# PCB_Vigne_Periph.net
KiCad netlist of a schematic drawn in Altium Designer
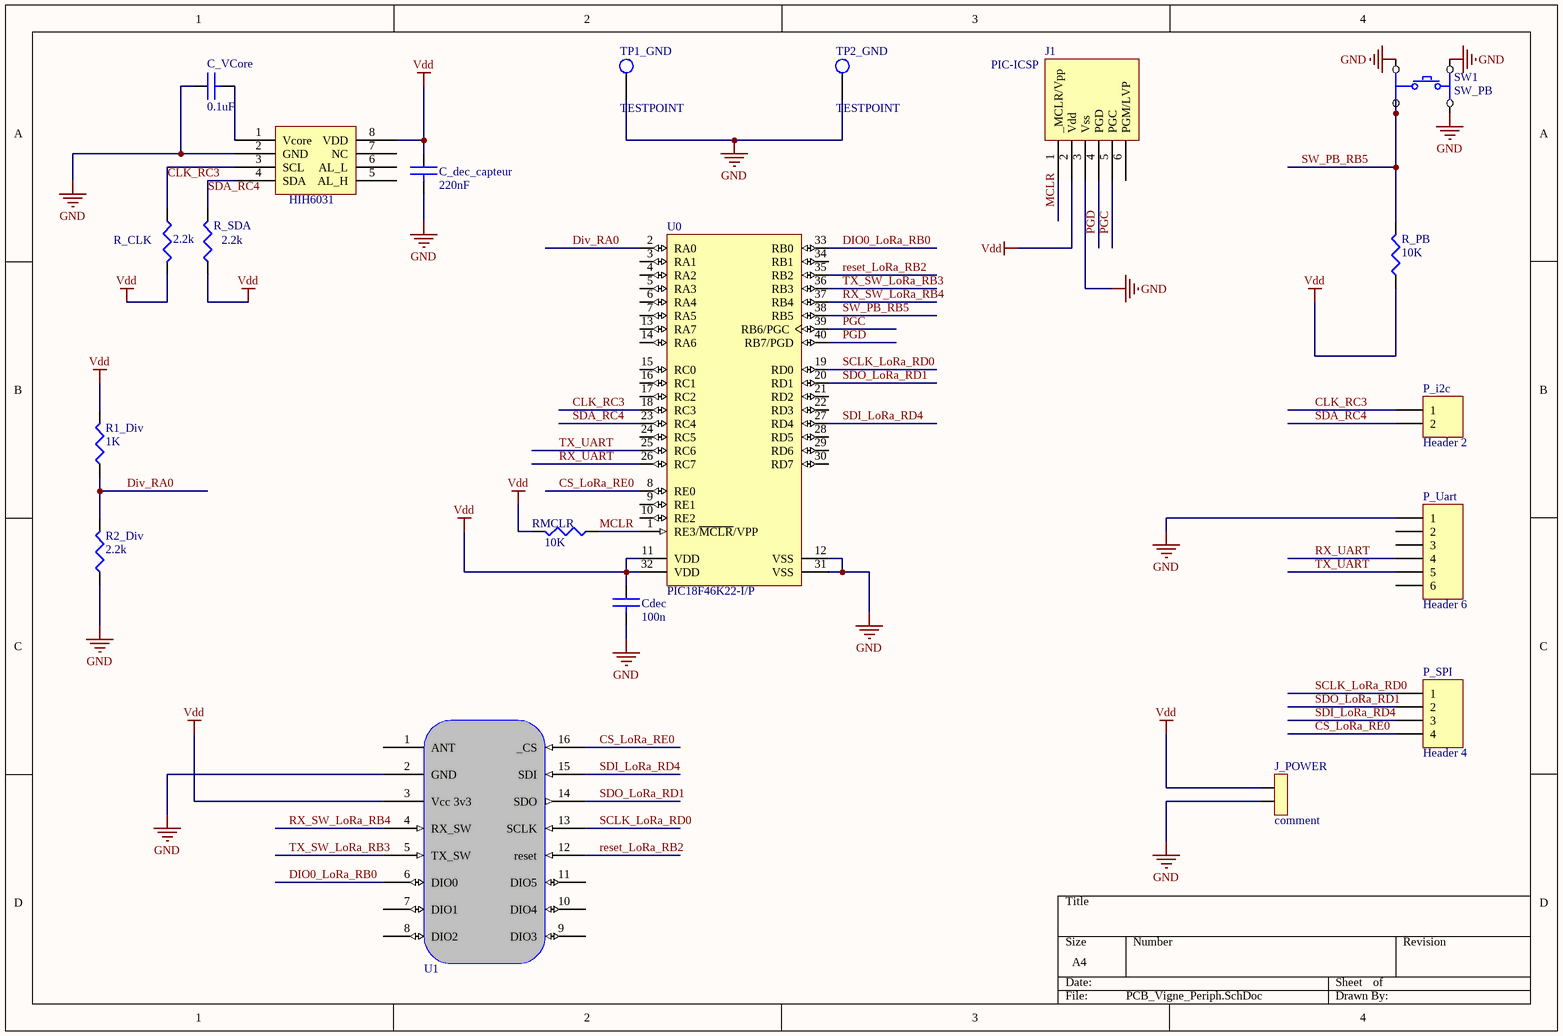
[diagram p0: PCB_Vigne_Periph.SchDoc]

(export (version "E")
  (design (tool "Eeschema 10.0.6"))
  (components
    (comp (ref "Cdec")
      (value "100n")
      (footprint "RAD0.2")
      (description "capacité non polarisée")
      (fields (field (name "Comment") "CAP"))
      (libsource (lib "ISEN_basics") (part "CAP"))
    )
    (comp (ref "C_dec_capteur")
      (value "220nF")
      (footprint "RAD0.2")
      (description "capacité non polarisée")
      (fields (field (name "Comment") "CAP"))
      (libsource (lib "ISEN_basics") (part "CAP"))
    )
    (comp (ref "C_VCore")
      (value "0.1uF")
      (footprint "RAD0.2")
      (description "capacité non polarisée")
      (fields (field (name "Comment") "CAP"))
      (libsource (lib "ISEN_basics") (part "CAP"))
    )
    (comp (ref "HIH6031")
      (value "HIH6031")
      (footprint "HIH6031-Traversant")
      (libsource (lib "HIH6031") (part "HIH6031"))
    )
    (comp (ref "J1")
      (value "PIC-ICSP")
      (footprint "PIC-ICSP")
      (libsource (lib "ISEN_basics") (part "PIC-ICSP"))
    )
    (comp (ref "J_POWER")
      (value "comment")
      (footprint "AMP_2")
      (description "connecteur alim 2 pôles")
      (libsource (lib "ISEN_basics") (part "POWER2"))
    )
    (comp (ref "P_i2c")
      (value "Header 2")
      (footprint "HDR1X2")
      (description "Header, 2-Pin")
      (fields (field (name "PUBLISHER") "Altium Limited"))
      (libsource (lib "Miscellaneous Connectors") (part "Header 2"))
    )
    (comp (ref "P_SPI")
      (value "Header 4")
      (footprint "HDR1X4")
      (description "Header, 4-Pin")
      (fields (field (name "PUBLISHER") "Altium Limited"))
      (libsource (lib "Miscellaneous Connectors") (part "Header 4"))
    )
    (comp (ref "P_Uart")
      (value "Header 6")
      (footprint "HDR1X6")
      (description "Header, 6-Pin")
      (fields (field (name "PUBLISHER") "Altium Limited"))
      (libsource (lib "Miscellaneous Connectors") (part "Header 6"))
    )
    (comp (ref "R1_Div")
      (value "1K")
      (footprint "AXIAL0.4")
      (description "resistance")
      (fields (field (name "Comment") "RES"))
      (libsource (lib "ISEN_basics") (part "RES"))
    )
    (comp (ref "R2_Div")
      (value "2.2k")
      (footprint "AXIAL0.4")
      (description "resistance")
      (fields (field (name "Comment") "RES"))
      (libsource (lib "ISEN_basics") (part "RES"))
    )
    (comp (ref "RMCLR")
      (value "10K")
      (footprint "AXIAL0.4")
      (description "resistance")
      (fields (field (name "Comment") "RES"))
      (libsource (lib "ISEN_basicsIntLib") (part "RES"))
    )
    (comp (ref "R_CLK")
      (value "2.2k")
      (footprint "AXIAL0.4")
      (description "resistance")
      (fields (field (name "Comment") "RES"))
      (libsource (lib "ISEN_basics") (part "RES"))
    )
    (comp (ref "R_PB")
      (value "10K")
      (footprint "AXIAL0.4")
      (description "resistance")
      (fields (field (name "Comment") "RES"))
      (libsource (lib "ISEN_basics") (part "RES"))
    )
    (comp (ref "R_SDA")
      (value "2.2k")
      (footprint "AXIAL0.4")
      (description "resistance")
      (fields (field (name "Comment") "RES"))
      (libsource (lib "ISEN_basics") (part "RES"))
    )
    (comp (ref "SW1") (value "SW_PB") (footprint "KSA") (libsource (lib "ISEN_basics") (part "SW_PB")))
    (comp (ref "TP1_GND")
      (value "TESTPOINT")
      (footprint "testpoint")
      (libsource (lib "ISEN_basics") (part "TESTPOINT"))
    )
    (comp (ref "TP2_GND")
      (value "TESTPOINT")
      (footprint "testpoint")
      (libsource (lib "ISEN_basics") (part "TESTPOINT"))
    )
    (comp (ref "U0")
      (value "PIC18F46K22-I/P")
      (footprint "MCHP-PDIP-P40")
      (fields (field (name "MANUFACTURER") "Microchip"))
      (libsource (lib "Microchip PIC18") (part "PIC18F46K22-I/P"))
    )
    (comp (ref "U1")
      (value "RF-LORA-868-SO")
      (footprint "RF-LORA-868-DIP")
      (libsource (lib "ISEN_basics") (part "RF-LORA-868-SO"))
    )
  )
  (nets
    (net (code "1") (name "/CLK_RC3") (class "Default")
      (node (ref "HIH6031") (pin "3") (pinfunction "SCL_3") (pintype "passive"))
      (node (ref "P_i2c") (pin "1") (pinfunction "1_1") (pintype "passive"))
      (node (ref "R_CLK") (pin "1") (pintype "passive"))
      (node (ref "U0") (pin "18") (pinfunction "RC3_18") (pintype "bidirectional"))
    )
    (net (code "2") (name "/CS_LoRa_RE0") (class "Default")
      (node (ref "P_SPI") (pin "4") (pinfunction "4_4") (pintype "passive"))
      (node (ref "U0") (pin "8") (pinfunction "RE0_8") (pintype "bidirectional"))
      (node (ref "U1") (pin "16") (pinfunction "_CS_16") (pintype "input"))
    )
    (net (code "3") (name "/DIO0_LoRa_RB0") (class "Default")
      (node (ref "U0") (pin "33") (pinfunction "RB0_33") (pintype "bidirectional"))
      (node (ref "U1") (pin "6") (pinfunction "DIO0_6") (pintype "bidirectional"))
    )
    (net (code "4") (name "/Div_RA0") (class "Default")
      (node (ref "R1_Div") (pin "1") (pintype "passive"))
      (node (ref "R2_Div") (pin "2") (pintype "passive"))
      (node (ref "U0") (pin "2") (pinfunction "RA0_2") (pintype "bidirectional"))
    )
    (net (code "5") (name "/MCLR") (class "Default")
      (node (ref "J1") (pin "1") (pinfunction "_MCLR/Vpp_1") (pintype "passive"))
      (node (ref "RMCLR") (pin "1") (pintype "passive"))
      (node (ref "U0") (pin "1") (pinfunction "RE3/~{MCLR}/VPP_1") (pintype "input"))
    )
    (net (code "6") (name "/PGC") (class "Default")
      (node (ref "J1") (pin "5") (pinfunction "PGC_5") (pintype "passive"))
      (node (ref "U0") (pin "39") (pinfunction "RB6/PGC_39") (pintype "bidirectional"))
    )
    (net (code "7") (name "/PGD") (class "Default")
      (node (ref "J1") (pin "4") (pinfunction "PGD_4") (pintype "passive"))
      (node (ref "U0") (pin "40") (pinfunction "RB7/PGD_40") (pintype "bidirectional"))
    )
    (net (code "8") (name "/RX_SW_LoRa_RB4") (class "Default")
      (node (ref "U0") (pin "37") (pinfunction "RB4_37") (pintype "bidirectional"))
      (node (ref "U1") (pin "4") (pinfunction "RX_SW_4") (pintype "input"))
    )
    (net (code "9") (name "/RX_UART") (class "Default")
      (node (ref "P_Uart") (pin "4") (pinfunction "4_4") (pintype "passive"))
      (node (ref "U0") (pin "26") (pinfunction "RC7_26") (pintype "bidirectional"))
    )
    (net (code "10") (name "/SCLK_LoRa_RD0") (class "Default")
      (node (ref "P_SPI") (pin "1") (pinfunction "1_1") (pintype "passive"))
      (node (ref "U0") (pin "19") (pinfunction "RD0_19") (pintype "bidirectional"))
      (node (ref "U1") (pin "13") (pinfunction "SCLK_13") (pintype "input"))
    )
    (net (code "11") (name "/SDA_RC4") (class "Default")
      (node (ref "HIH6031") (pin "4") (pinfunction "SDA_4") (pintype "passive"))
      (node (ref "P_i2c") (pin "2") (pinfunction "2_2") (pintype "passive"))
      (node (ref "R_SDA") (pin "2") (pintype "passive"))
      (node (ref "U0") (pin "23") (pinfunction "RC4_23") (pintype "bidirectional"))
    )
    (net (code "12") (name "/SDI_LoRa_RD4") (class "Default")
      (node (ref "P_SPI") (pin "3") (pinfunction "3_3") (pintype "passive"))
      (node (ref "U0") (pin "27") (pinfunction "RD4_27") (pintype "bidirectional"))
      (node (ref "U1") (pin "15") (pinfunction "SDI_15") (pintype "input"))
    )
    (net (code "13") (name "/SDO_LoRa_RD1") (class "Default")
      (node (ref "P_SPI") (pin "2") (pinfunction "2_2") (pintype "passive"))
      (node (ref "U0") (pin "20") (pinfunction "RD1_20") (pintype "bidirectional"))
      (node (ref "U1") (pin "14") (pinfunction "SDO_14") (pintype "output"))
    )
    (net (code "14") (name "/SW_PB_RB5") (class "Default")
      (node (ref "R_PB") (pin "2") (pintype "passive"))
      (node (ref "SW1") (pin "2") (pintype "passive"))
      (node (ref "U0") (pin "38") (pinfunction "RB5_38") (pintype "bidirectional"))
    )
    (net (code "15") (name "/TX_SW_LoRa_RB3") (class "Default")
      (node (ref "U0") (pin "36") (pinfunction "RB3_36") (pintype "bidirectional"))
      (node (ref "U1") (pin "5") (pinfunction "TX_SW_5") (pintype "input"))
    )
    (net (code "16") (name "/TX_UART") (class "Default")
      (node (ref "P_Uart") (pin "5") (pinfunction "5_5") (pintype "passive"))
      (node (ref "U0") (pin "25") (pinfunction "RC6_25") (pintype "bidirectional"))
    )
    (net (code "17") (name "/reset_LoRa_RB2") (class "Default")
      (node (ref "U0") (pin "35") (pinfunction "RB2_35") (pintype "bidirectional"))
      (node (ref "U1") (pin "12") (pinfunction "reset_12") (pintype "input"))
    )
    (net (code "18") (name "GND") (class "Default")
      (node (ref "C_VCore") (pin "1") (pinfunction "1_1") (pintype "passive"))
      (node (ref "C_dec_capteur") (pin "2") (pinfunction "2_2") (pintype "passive"))
      (node (ref "Cdec") (pin "2") (pinfunction "2_2") (pintype "passive"))
      (node (ref "HIH6031") (pin "2") (pinfunction "GND_2") (pintype "passive"))
      (node (ref "J1") (pin "3") (pinfunction "Vss_3") (pintype "passive"))
      (node (ref "J_POWER") (pin "1") (pintype "passive"))
      (node (ref "P_Uart") (pin "1") (pinfunction "1_1") (pintype "passive"))
      (node (ref "R2_Div") (pin "1") (pintype "passive"))
      (node (ref "SW1") (pin "1") (pintype "passive"))
      (node (ref "SW1") (pin "3") (pintype "passive"))
      (node (ref "SW1") (pin "4") (pintype "passive"))
      (node (ref "TP1_GND") (pin "1") (pintype "passive"))
      (node (ref "TP2_GND") (pin "1") (pintype "passive"))
      (node (ref "U0") (pin "12") (pinfunction "VSS_12") (pintype "power_in"))
      (node (ref "U0") (pin "31") (pinfunction "VSS_31") (pintype "power_in"))
      (node (ref "U1") (pin "2") (pinfunction "GND_2") (pintype "power_in"))
    )
    (net (code "19") (name "Net-(HIH6031-Vcore)") (class "Default")
      (node (ref "C_VCore") (pin "2") (pinfunction "2_2") (pintype "passive"))
      (node (ref "HIH6031") (pin "1") (pinfunction "Vcore_1") (pintype "passive"))
    )
    (net (code "20") (name "Vdd") (class "Default")
      (node (ref "C_dec_capteur") (pin "1") (pinfunction "1_1") (pintype "passive"))
      (node (ref "Cdec") (pin "1") (pinfunction "1_1") (pintype "passive"))
      (node (ref "HIH6031") (pin "8") (pinfunction "VDD_8") (pintype "passive"))
      (node (ref "J1") (pin "2") (pinfunction "Vdd_2") (pintype "passive"))
      (node (ref "J_POWER") (pin "2") (pintype "passive"))
      (node (ref "R1_Div") (pin "2") (pintype "passive"))
      (node (ref "RMCLR") (pin "2") (pintype "passive"))
      (node (ref "R_CLK") (pin "2") (pintype "passive"))
      (node (ref "R_PB") (pin "1") (pintype "passive"))
      (node (ref "R_SDA") (pin "1") (pintype "passive"))
      (node (ref "U0") (pin "11") (pinfunction "VDD_11") (pintype "power_in"))
      (node (ref "U0") (pin "32") (pinfunction "VDD_32") (pintype "power_in"))
      (node (ref "U1") (pin "3") (pinfunction "Vcc_3v3_3") (pintype "power_in"))
    )
    (net (code "21") (name "unconnected-(HIH6031-AL_H-Pad5)") (class "Default")
      (node (ref "HIH6031") (pin "5") (pinfunction "AL_H_5") (pintype "passive"))
    )
    (net (code "22") (name "unconnected-(HIH6031-AL_L-Pad6)") (class "Default")
      (node (ref "HIH6031") (pin "6") (pinfunction "AL_L_6") (pintype "passive"))
    )
    (net (code "23") (name "unconnected-(HIH6031-NC-Pad7)") (class "Default")
      (node (ref "HIH6031") (pin "7") (pinfunction "NC_7") (pintype "passive"))
    )
    (net (code "24") (name "unconnected-(J1-PGM{slash}LVP-Pad6)") (class "Default")
      (node (ref "J1") (pin "6") (pinfunction "PGM/LVP_6") (pintype "passive"))
    )
    (net (code "25") (name "unconnected-(P_Uart-Pad2)") (class "Default")
      (node (ref "P_Uart") (pin "2") (pinfunction "2_2") (pintype "passive"))
    )
    (net (code "26") (name "unconnected-(P_Uart-Pad3)") (class "Default")
      (node (ref "P_Uart") (pin "3") (pinfunction "3_3") (pintype "passive"))
    )
    (net (code "27") (name "unconnected-(P_Uart-Pad6)") (class "Default")
      (node (ref "P_Uart") (pin "6") (pinfunction "6_6") (pintype "passive"))
    )
    (net (code "28") (name "unconnected-(U0-RA1-Pad3)") (class "Default")
      (node (ref "U0") (pin "3") (pinfunction "RA1_3") (pintype "bidirectional"))
    )
    (net (code "29") (name "unconnected-(U0-RA2-Pad4)") (class "Default")
      (node (ref "U0") (pin "4") (pinfunction "RA2_4") (pintype "bidirectional"))
    )
    (net (code "30") (name "unconnected-(U0-RA3-Pad5)") (class "Default")
      (node (ref "U0") (pin "5") (pinfunction "RA3_5") (pintype "bidirectional"))
    )
    (net (code "31") (name "unconnected-(U0-RA4-Pad6)") (class "Default")
      (node (ref "U0") (pin "6") (pinfunction "RA4_6") (pintype "bidirectional"))
    )
    (net (code "32") (name "unconnected-(U0-RA5-Pad7)") (class "Default")
      (node (ref "U0") (pin "7") (pinfunction "RA5_7") (pintype "bidirectional"))
    )
    (net (code "33") (name "unconnected-(U0-RA6-Pad14)") (class "Default")
      (node (ref "U0") (pin "14") (pinfunction "RA6_14") (pintype "bidirectional"))
    )
    (net (code "34") (name "unconnected-(U0-RA7-Pad13)") (class "Default")
      (node (ref "U0") (pin "13") (pinfunction "RA7_13") (pintype "bidirectional"))
    )
    (net (code "35") (name "unconnected-(U0-RB1-Pad34)") (class "Default")
      (node (ref "U0") (pin "34") (pinfunction "RB1_34") (pintype "bidirectional"))
    )
    (net (code "36") (name "unconnected-(U0-RC0-Pad15)") (class "Default")
      (node (ref "U0") (pin "15") (pinfunction "RC0_15") (pintype "bidirectional"))
    )
    (net (code "37") (name "unconnected-(U0-RC1-Pad16)") (class "Default")
      (node (ref "U0") (pin "16") (pinfunction "RC1_16") (pintype "bidirectional"))
    )
    (net (code "38") (name "unconnected-(U0-RC2-Pad17)") (class "Default")
      (node (ref "U0") (pin "17") (pinfunction "RC2_17") (pintype "bidirectional"))
    )
    (net (code "39") (name "unconnected-(U0-RC5-Pad24)") (class "Default")
      (node (ref "U0") (pin "24") (pinfunction "RC5_24") (pintype "bidirectional"))
    )
    (net (code "40") (name "unconnected-(U0-RD2-Pad21)") (class "Default")
      (node (ref "U0") (pin "21") (pinfunction "RD2_21") (pintype "bidirectional"))
    )
    (net (code "41") (name "unconnected-(U0-RD3-Pad22)") (class "Default")
      (node (ref "U0") (pin "22") (pinfunction "RD3_22") (pintype "bidirectional"))
    )
    (net (code "42") (name "unconnected-(U0-RD5-Pad28)") (class "Default")
      (node (ref "U0") (pin "28") (pinfunction "RD5_28") (pintype "bidirectional"))
    )
    (net (code "43") (name "unconnected-(U0-RD6-Pad29)") (class "Default")
      (node (ref "U0") (pin "29") (pinfunction "RD6_29") (pintype "bidirectional"))
    )
    (net (code "44") (name "unconnected-(U0-RD7-Pad30)") (class "Default")
      (node (ref "U0") (pin "30") (pinfunction "RD7_30") (pintype "bidirectional"))
    )
    (net (code "45") (name "unconnected-(U0-RE1-Pad9)") (class "Default")
      (node (ref "U0") (pin "9") (pinfunction "RE1_9") (pintype "bidirectional"))
    )
    (net (code "46") (name "unconnected-(U0-RE2-Pad10)") (class "Default")
      (node (ref "U0") (pin "10") (pinfunction "RE2_10") (pintype "bidirectional"))
    )
    (net (code "47") (name "unconnected-(U1-ANT-Pad1)") (class "Default")
      (node (ref "U1") (pin "1") (pinfunction "ANT_1") (pintype "passive"))
    )
    (net (code "48") (name "unconnected-(U1-DIO1-Pad7)") (class "Default")
      (node (ref "U1") (pin "7") (pinfunction "DIO1_7") (pintype "bidirectional"))
    )
    (net (code "49") (name "unconnected-(U1-DIO2-Pad8)") (class "Default")
      (node (ref "U1") (pin "8") (pinfunction "DIO2_8") (pintype "bidirectional"))
    )
    (net (code "50") (name "unconnected-(U1-DIO3-Pad9)") (class "Default")
      (node (ref "U1") (pin "9") (pinfunction "DIO3_9") (pintype "bidirectional"))
    )
    (net (code "51") (name "unconnected-(U1-DIO4-Pad10)") (class "Default")
      (node (ref "U1") (pin "10") (pinfunction "DIO4_10") (pintype "bidirectional"))
    )
    (net (code "52") (name "unconnected-(U1-DIO5-Pad11)") (class "Default")
      (node (ref "U1") (pin "11") (pinfunction "DIO5_11") (pintype "bidirectional"))
    )
  )
)
